# audio.net
KiCad netlist of a schematic drawn in Altium Designer
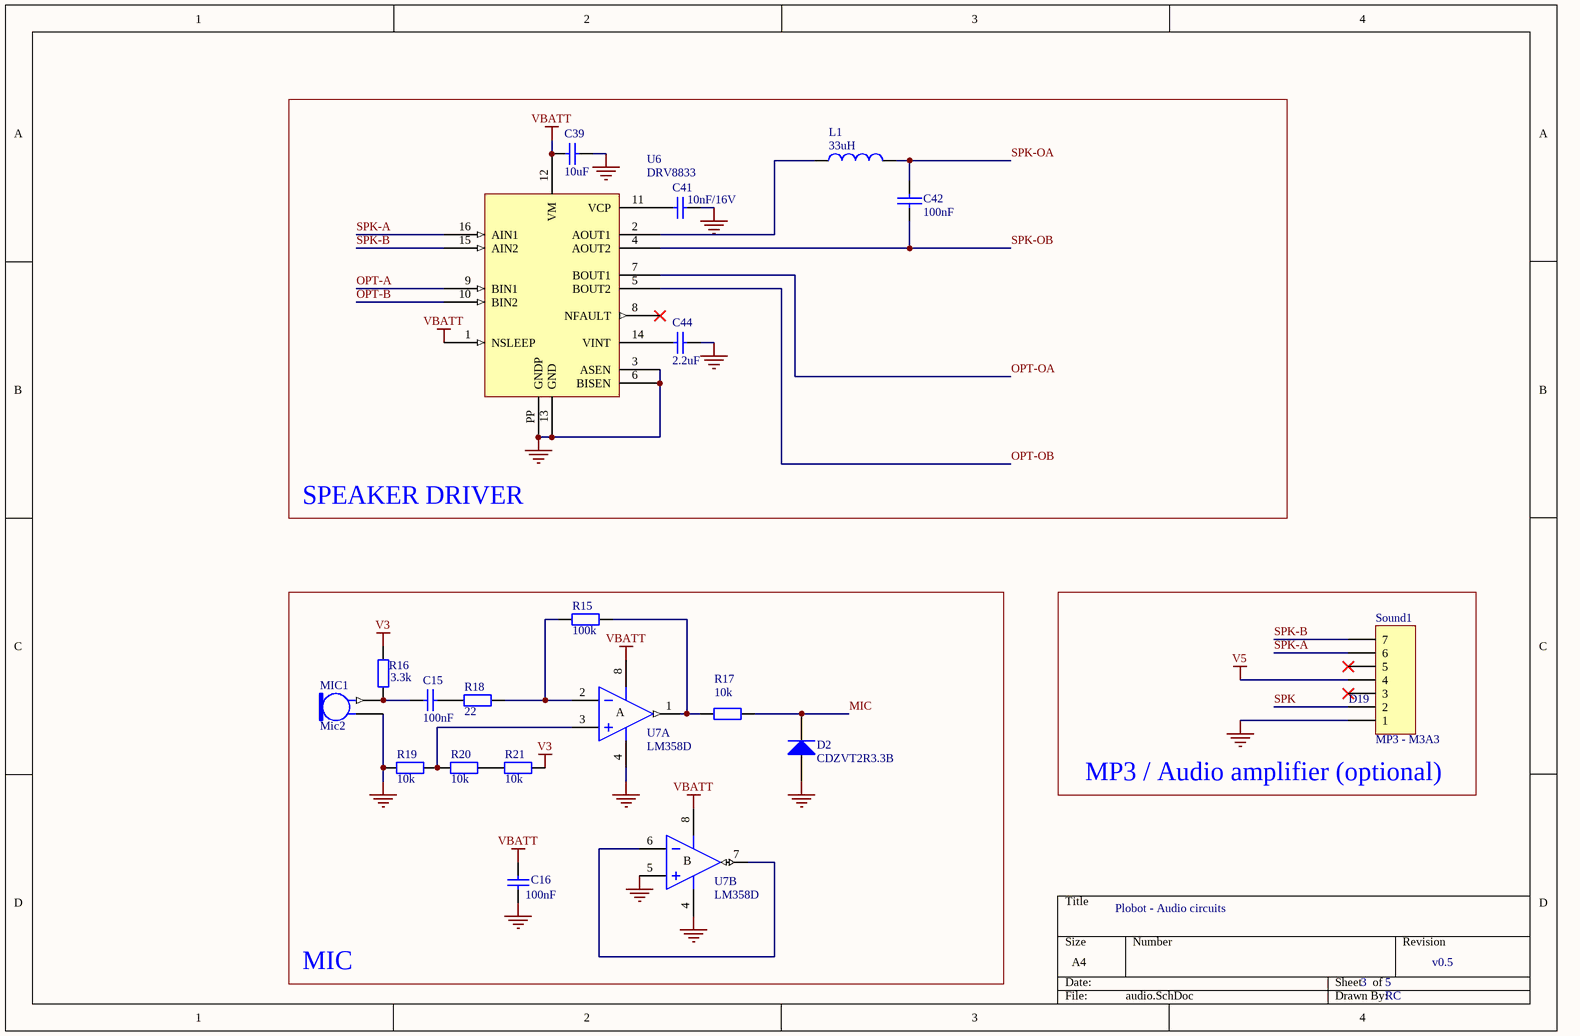
[diagram p0: audio.SchDoc]

(export (version "E")
  (design (tool "Eeschema 10.0.6"))
  (components
    (comp (ref "C15")
      (value "100nF")
      (footprint "plobot_review:CAPC1608N")
      (description "Capacitor")
      (fields (field (name "PUBLISHER") "Altium Limited"))
      (libsource (lib "*") (part "Cap"))
    )
    (comp (ref "C16")
      (value "100nF")
      (footprint "plobot_review:CAPC1608N")
      (description "Capacitor")
      (fields (field (name "PUBLISHER") "Altium Limited"))
      (libsource (lib "") (part "Cap_1"))
    )
    (comp (ref "C39")
      (value "10uF")
      (footprint "plobot_review:CAPC3216N")
      (description "Capacitor")
      (fields (field (name "PUBLISHER") "Altium Limited"))
      (libsource (lib "main_pcb") (part "Cap_2"))
    )
    (comp (ref "C41")
      (value "10nF/16V")
      (footprint "plobot_review:CAPC2012N")
      (description "Capacitor")
      (fields (field (name "PUBLISHER") "Altium Limited"))
      (libsource (lib "") (part "Cap_1"))
    )
    (comp (ref "C42")
      (value "100nF")
      (footprint "plobot_review:CAPC1608N")
      (description "Capacitor")
      (libsource (lib "") (part "Cap_2"))
    )
    (comp (ref "C44")
      (value "2.2uF")
      (footprint "plobot_review:CAPC2012N")
      (description "Capacitor")
      (fields (field (name "PUBLISHER") "Altium Limited"))
      (libsource (lib "") (part "Cap_1"))
    )
    (comp (ref "D2")
      (value "CDZVT2R3.3B")
      (footprint "plobot_review:SOD123/X.85")
      (description "Default Diode")
      (fields (field (name "PUBLISHER") "Altium Limited"))
      (libsource (lib "Miscellaneous Devices") (part "Diode"))
    )
    (comp (ref "L1")
      (value "33uH")
      (footprint "plobot_review:INDC1608N")
      (description "Inductor")
      (fields (field (name "PUBLISHER") "Altium Limited"))
      (libsource (lib "Miscellaneous Devices") (part "Inductor"))
    )
    (comp (ref "MIC1")
      (value "Mic2")
      (footprint "plobot_review:electret_6mm")
      (description "Microphone")
      (fields (field (name "PUBLISHER") "*"))
      (libsource (lib "*") (part "Mic2"))
    )
    (comp (ref "R15")
      (value "100k")
      (footprint "plobot_review:RESC1608N")
      (description "Resistor")
      (fields (field (name "PUBLISHER") "Altium Limited"))
      (libsource (lib "*") (part "Res2"))
    )
    (comp (ref "R16")
      (value "3.3k")
      (footprint "plobot_review:RESC1608N")
      (description "Resistor")
      (fields (field (name "PUBLISHER") "Altium Limited"))
      (libsource (lib "") (part "Res2_1"))
    )
    (comp (ref "R17")
      (value "10k")
      (footprint "plobot_review:RESC1608N")
      (description "Resistor")
      (fields (field (name "PUBLISHER") "Altium Limited"))
      (libsource (lib "*") (part "Res2"))
    )
    (comp (ref "R18")
      (value "22")
      (footprint "plobot_review:RESC1608N")
      (description "Resistor")
      (fields (field (name "PUBLISHER") "Altium Limited"))
      (libsource (lib "*") (part "Res2"))
    )
    (comp (ref "R19")
      (value "10k")
      (footprint "plobot_review:RESC1608N")
      (description "Resistor")
      (fields (field (name "PUBLISHER") "Altium Limited"))
      (libsource (lib "*") (part "Res2"))
    )
    (comp (ref "R20")
      (value "10k")
      (footprint "plobot_review:RESC1608N")
      (description "Resistor")
      (fields (field (name "PUBLISHER") "Altium Limited"))
      (libsource (lib "*") (part "Res2"))
    )
    (comp (ref "R21")
      (value "10k")
      (footprint "plobot_review:RESC1608N")
      (description "Resistor")
      (fields (field (name "PUBLISHER") "Altium Limited"))
      (libsource (lib "*") (part "Res2"))
    )
    (comp (ref "Sound1")
      (value "MP3 - M3A3")
      (footprint "plobot_review:MP3")
      (description "Header, 7-Pin")
      (libsource (lib "Miscellaneous Connectors") (part "Header 7"))
    )
    (comp (ref "U6")
      (value "DRV8833")
      (footprint "plobot_review:DRV8833")
      (libsource (lib "components") (part "DRV8833"))
    )
    (comp (ref "U7")
      (value "LM358D")
      (footprint "plobot_review:LM358D")
      (description "Dual Operational Amplifier")
      (fields (field (name "PUBLISHER") "Altium Limited"))
      (libsource (lib "TI Operational Amplifier") (part "LM358D"))
    )
  )
  (nets
    (net (code "1") (name "/MIC") (class "Default")
      (node (ref "D2") (pin "1") (pinfunction "K_1") (pintype "passive"))
      (node (ref "R17") (pin "2") (pinfunction "2_2") (pintype "passive"))
    )
    (net (code "2") (name "/OPT-A") (class "Default")
      (node (ref "U6") (pin "9") (pinfunction "BIN1_9") (pintype "input"))
    )
    (net (code "3") (name "/OPT-B") (class "Default")
      (node (ref "U6") (pin "10") (pinfunction "BIN2_10") (pintype "input"))
    )
    (net (code "4") (name "/OPT-OA") (class "Default")
      (node (ref "U6") (pin "7") (pinfunction "BOUT1_7") (pintype "power_in"))
    )
    (net (code "5") (name "/OPT-OB") (class "Default")
      (node (ref "U6") (pin "5") (pinfunction "BOUT2_5") (pintype "power_in"))
    )
    (net (code "6") (name "/SPK") (class "Default")
      (node (ref "Sound1") (pin "2") (pinfunction "2_2") (pintype "passive"))
    )
    (net (code "7") (name "/SPK-A") (class "Default")
      (node (ref "Sound1") (pin "6") (pinfunction "6_6") (pintype "passive"))
      (node (ref "U6") (pin "16") (pinfunction "AIN1_16") (pintype "input"))
    )
    (net (code "8") (name "/SPK-B") (class "Default")
      (node (ref "Sound1") (pin "7") (pinfunction "7_7") (pintype "passive"))
      (node (ref "U6") (pin "15") (pinfunction "AIN2_15") (pintype "input"))
    )
    (net (code "9") (name "/SPK-OA") (class "Default")
      (node (ref "C42") (pin "2") (pinfunction "2_2") (pintype "passive"))
      (node (ref "L1") (pin "2") (pinfunction "2_2") (pintype "passive"))
    )
    (net (code "10") (name "/SPK-OB") (class "Default")
      (node (ref "C42") (pin "1") (pinfunction "1_1") (pintype "passive"))
      (node (ref "U6") (pin "4") (pinfunction "AOUT2_4") (pintype "power_in"))
    )
    (net (code "11") (name "GND") (class "Default")
      (node (ref "C16") (pin "2") (pinfunction "2_2") (pintype "passive"))
      (node (ref "C39") (pin "1") (pinfunction "1_1") (pintype "passive"))
      (node (ref "C41") (pin "1") (pinfunction "1_1") (pintype "passive"))
      (node (ref "C44") (pin "1") (pinfunction "1_1") (pintype "passive"))
      (node (ref "D2") (pin "2") (pinfunction "A_2") (pintype "passive"))
      (node (ref "MIC1") (pin "2") (pinfunction "2_2") (pintype "power_in"))
      (node (ref "R19") (pin "1") (pinfunction "1_1") (pintype "passive"))
      (node (ref "Sound1") (pin "1") (pinfunction "1_1") (pintype "passive"))
      (node (ref "U6") (pin "13") (pinfunction "GND_13") (pintype "power_in"))
      (node (ref "U6") (pin "3") (pinfunction "ASEN_3") (pintype "power_in"))
      (node (ref "U6") (pin "6") (pinfunction "BISEN_6") (pintype "power_in"))
      (node (ref "U6") (pin "PP") (pinfunction "GNDP_PP") (pintype "power_in"))
      (node (ref "U7") (pin "4") (pinfunction "V-_4") (pintype "power_in"))
      (node (ref "U7") (pin "5") (pinfunction "IN+_5") (pintype "passive"))
    )
    (net (code "12") (name "Net-(C15-Pad1)") (class "Default")
      (node (ref "C15") (pin "1") (pinfunction "1_1") (pintype "passive"))
      (node (ref "R18") (pin "1") (pinfunction "1_1") (pintype "passive"))
    )
    (net (code "13") (name "Net-(C15-Pad2)") (class "Default")
      (node (ref "C15") (pin "2") (pinfunction "2_2") (pintype "passive"))
      (node (ref "MIC1") (pin "1") (pinfunction "1_1") (pintype "output"))
      (node (ref "R16") (pin "2") (pinfunction "2_2") (pintype "passive"))
    )
    (net (code "14") (name "Net-(R20-Pad2)") (class "Default")
      (node (ref "R20") (pin "2") (pinfunction "2_2") (pintype "passive"))
      (node (ref "R21") (pin "1") (pinfunction "1_1") (pintype "passive"))
    )
    (net (code "15") (name "Net-(U6-AOUT1)") (class "Default")
      (node (ref "L1") (pin "1") (pinfunction "1_1") (pintype "passive"))
      (node (ref "U6") (pin "2") (pinfunction "AOUT1_2") (pintype "power_in"))
    )
    (net (code "16") (name "Net-(U6-VCP)") (class "Default")
      (node (ref "C41") (pin "2") (pinfunction "2_2") (pintype "passive"))
      (node (ref "U6") (pin "11") (pinfunction "VCP_11") (pintype "power_in"))
    )
    (net (code "17") (name "Net-(U6-VINT)") (class "Default")
      (node (ref "C44") (pin "2") (pinfunction "2_2") (pintype "passive"))
      (node (ref "U6") (pin "14") (pinfunction "VINT_14") (pintype "power_in"))
    )
    (net (code "18") (name "Net-(U7A-IN+)") (class "Default")
      (node (ref "R19") (pin "2") (pinfunction "2_2") (pintype "passive"))
      (node (ref "R20") (pin "1") (pinfunction "1_1") (pintype "passive"))
      (node (ref "U7") (pin "3") (pinfunction "IN+_3") (pintype "passive"))
    )
    (net (code "19") (name "Net-(U7A-IN-)") (class "Default")
      (node (ref "R15") (pin "1") (pinfunction "1_1") (pintype "passive"))
      (node (ref "R18") (pin "2") (pinfunction "2_2") (pintype "passive"))
      (node (ref "U7") (pin "2") (pinfunction "IN-_2") (pintype "passive"))
    )
    (net (code "20") (name "Net-(U7A-OUT)") (class "Default")
      (node (ref "R15") (pin "2") (pinfunction "2_2") (pintype "passive"))
      (node (ref "R17") (pin "1") (pinfunction "1_1") (pintype "passive"))
      (node (ref "U7") (pin "1") (pinfunction "OUT_1") (pintype "output"))
    )
    (net (code "21") (name "Net-(U7B-IN-)") (class "Default")
      (node (ref "U7") (pin "6") (pinfunction "IN-_6") (pintype "passive"))
      (node (ref "U7") (pin "7") (pinfunction "OUT_7") (pintype "bidirectional"))
    )
    (net (code "22") (name "V3") (class "Default")
      (node (ref "R16") (pin "1") (pinfunction "1_1") (pintype "passive"))
      (node (ref "R21") (pin "2") (pinfunction "2_2") (pintype "passive"))
    )
    (net (code "23") (name "V5") (class "Default")
      (node (ref "Sound1") (pin "4") (pinfunction "4_4") (pintype "passive"))
    )
    (net (code "24") (name "VBATT") (class "Default")
      (node (ref "C16") (pin "1") (pinfunction "1_1") (pintype "passive"))
      (node (ref "C39") (pin "2") (pinfunction "2_2") (pintype "passive"))
      (node (ref "U6") (pin "1") (pinfunction "NSLEEP_1") (pintype "input"))
      (node (ref "U6") (pin "12") (pinfunction "VM_12") (pintype "power_in"))
      (node (ref "U7") (pin "8") (pinfunction "V+_8") (pintype "power_in"))
    )
    (net (code "25") (name "unconnected-(Sound1-Pad3)") (class "Default")
      (node (ref "Sound1") (pin "3") (pinfunction "3_3") (pintype "passive+no_connect"))
    )
    (net (code "26") (name "unconnected-(Sound1-Pad5)") (class "Default")
      (node (ref "Sound1") (pin "5") (pinfunction "5_5") (pintype "passive+no_connect"))
    )
    (net (code "27") (name "unconnected-(U6-NFAULT-Pad8)") (class "Default")
      (node (ref "U6") (pin "8") (pinfunction "NFAULT_8") (pintype "output+no_connect"))
    )
  )
)
